# PetLaserBolt.net
KiCad netlist of a schematic drawn in Altium Designer
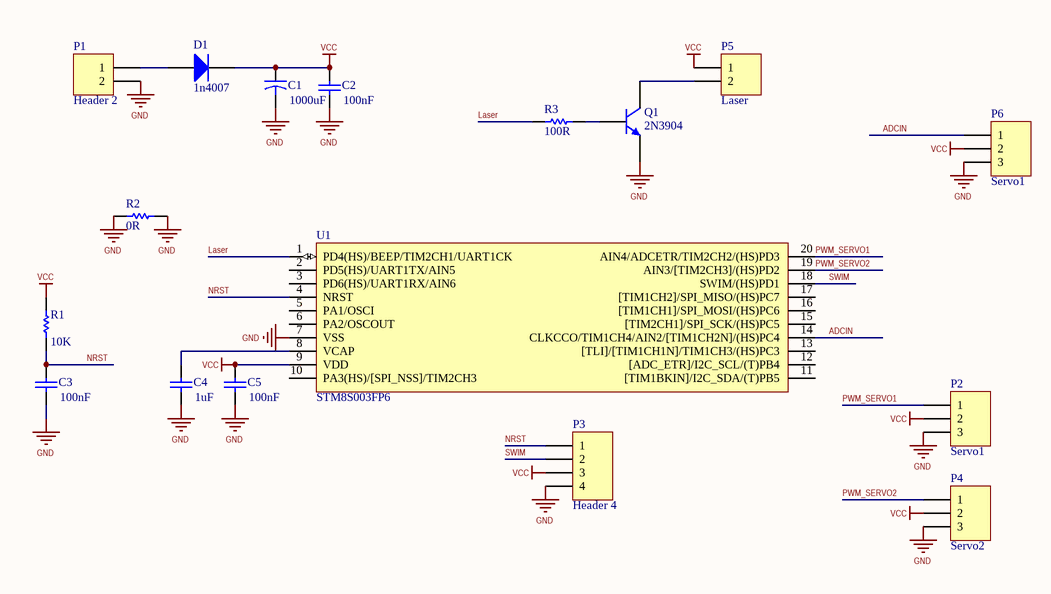
[diagram p0: PetLaserBolt.SchDoc]

(export (version "E")
  (design (tool "Eeschema 10.0.6"))
  (components
    (comp (ref "C1")
      (value "1000uF")
      (footprint "Cap electrolitic radial 10x16-5")
      (description "Capacitor")
      (fields (field (name "Comment") "Cap2") (field (name "PUBLISHER") "Altium Limited"))
      (libsource (lib "Miscellaneous Devices") (part "Cap2"))
    )
    (comp (ref "C2")
      (value "100nF")
      (footprint "CAP_MLCC_RAD_0.1")
      (description "Capacitor")
      (fields (field (name "Comment") "Cap") (field (name "PUBLISHER") "Altium Limited"))
      (libsource (lib "Miscellaneous Devices") (part "Cap"))
    )
    (comp (ref "C3")
      (value "100nF")
      (footprint "CAP_MLCC_RAD_0.1")
      (description "Capacitor")
      (fields (field (name "Comment") "Cap") (field (name "PUBLISHER") "Altium Limited"))
      (libsource (lib "Miscellaneous Devices") (part "Cap"))
    )
    (comp (ref "C4")
      (value "1uF")
      (footprint "CAP_MLCC_RAD_0.1")
      (description "Capacitor")
      (fields (field (name "Comment") "Cap") (field (name "PUBLISHER") "Altium Limited"))
      (libsource (lib "Miscellaneous Devices") (part "Cap"))
    )
    (comp (ref "C5")
      (value "100nF")
      (footprint "CAP_MLCC_RAD_0.1")
      (description "Capacitor")
      (fields (field (name "Comment") "Cap") (field (name "PUBLISHER") "Altium Limited"))
      (libsource (lib "Miscellaneous Devices") (part "Cap"))
    )
    (comp (ref "D1")
      (value "1n4007")
      (footprint "DO-204AL")
      (description "Default Diode")
      (fields (field (name "PUBLISHER") "Altium Limited"))
      (libsource (lib "Miscellaneous Devices") (part "Diode"))
    )
    (comp (ref "P1")
      (value "Header 2")
      (footprint "KF301 2PIN")
      (description "Header, 2-Pin")
      (fields (field (name "PUBLISHER") "Altium Limited"))
      (libsource (lib "Miscellaneous Connectors") (part "Header 2"))
    )
    (comp (ref "P2")
      (value "Servo1")
      (footprint "HDR_1x3")
      (description "Header, 3-Pin")
      (fields (field (name "PUBLISHER") "Altium Limited"))
      (libsource (lib "Miscellaneous Connectors") (part "Header 3"))
    )
    (comp (ref "P3")
      (value "Header 4")
      (footprint "HDR1X4")
      (description "Header, 4-Pin")
      (fields (field (name "PUBLISHER") "Altium Limited"))
      (libsource (lib "Miscellaneous Connectors") (part "Header 4"))
    )
    (comp (ref "P4")
      (value "Servo2")
      (footprint "HDR_1x3")
      (description "Header, 3-Pin")
      (fields (field (name "PUBLISHER") "Altium Limited"))
      (libsource (lib "Miscellaneous Connectors") (part "Header 3"))
    )
    (comp (ref "P5")
      (value "Laser")
      (footprint "KF301 2PIN")
      (description "Header, 2-Pin")
      (fields (field (name "PUBLISHER") "Altium Limited"))
      (libsource (lib "") (part "Header 2_1"))
    )
    (comp (ref "P6")
      (value "Servo1")
      (footprint "HDR_1x3")
      (description "Header, 3-Pin")
      (fields (field (name "PUBLISHER") "Altium Limited"))
      (libsource (lib "Miscellaneous Connectors") (part "Header 3"))
    )
    (comp (ref "Q1")
      (value "2N3904")
      (footprint "TO-92 STR")
      (description "NPN General Purpose Amplifier")
      (fields (field (name "PUBLISHER") "Altium Limited"))
      (libsource (lib "Miscellaneous Devices") (part "2N3904"))
    )
    (comp (ref "R1")
      (value "10K")
      (footprint "Axial 0_25 W, 0_4 IN LEAD PITCH")
      (description "Resistor")
      (fields (field (name "Comment") "Res1") (field (name "PUBLISHER") "Altium Limited"))
      (libsource (lib "Miscellaneous Devices") (part "Res1"))
    )
    (comp (ref "R2")
      (value "0R")
      (footprint "axial-0.3")
      (description "Resistor")
      (fields (field (name "Comment") "Res1") (field (name "PUBLISHER") "Altium Limited"))
      (libsource (lib "Miscellaneous Devices") (part "Res1"))
    )
    (comp (ref "R3")
      (value "100R")
      (footprint "Axial 0_25 W, 0_4 IN LEAD PITCH")
      (description "Resistor")
      (fields (field (name "Comment") "Res1") (field (name "PUBLISHER") "Altium Limited"))
      (libsource (lib "Miscellaneous Devices") (part "Res1"))
    )
    (comp (ref "U1")
      (value "STM8S003FP6")
      (footprint "TSSOP20")
      (description "8 bit microcontroller")
      (libsource (lib "Mofidi3D") (part "STM8S003F3Px"))
    )
  )
  (nets
    (net (code "1") (name "/ADCIN") (class "Default")
      (node (ref "P6") (pin "1") (pinfunction "1_1") (pintype "passive"))
      (node (ref "U1") (pin "14") (pinfunction "CLKCCO/TIM1CH4/AIN2/[TIM1CH2N]/(HS)PC4_14") (pintype "passive"))
    )
    (net (code "2") (name "/Laser") (class "Default")
      (node (ref "R3") (pin "2") (pinfunction "2_2") (pintype "passive"))
      (node (ref "U1") (pin "1") (pinfunction "PD4(HS)/BEEP/TIM2CH1/UART1CK_1") (pintype "bidirectional"))
    )
    (net (code "3") (name "/NRST") (class "Default")
      (node (ref "C3") (pin "2") (pinfunction "2_2") (pintype "passive"))
      (node (ref "P3") (pin "1") (pinfunction "1_1") (pintype "passive"))
      (node (ref "R1") (pin "1") (pinfunction "1_1") (pintype "passive"))
      (node (ref "U1") (pin "4") (pinfunction "NRST_4") (pintype "passive"))
    )
    (net (code "4") (name "/PWM_SERVO1") (class "Default")
      (node (ref "P2") (pin "1") (pinfunction "1_1") (pintype "passive"))
      (node (ref "U1") (pin "20") (pinfunction "AIN4/ADCETR/TIM2CH2/(HS)PD3_20") (pintype "passive"))
    )
    (net (code "5") (name "/PWM_SERVO2") (class "Default")
      (node (ref "P4") (pin "1") (pinfunction "1_1") (pintype "passive"))
      (node (ref "U1") (pin "19") (pinfunction "AIN3/[TIM2CH3]/(HS)PD2_19") (pintype "passive"))
    )
    (net (code "6") (name "/SWIM") (class "Default")
      (node (ref "P3") (pin "2") (pinfunction "2_2") (pintype "passive"))
      (node (ref "U1") (pin "18") (pinfunction "SWIM/(HS)PD1_18") (pintype "passive"))
    )
    (net (code "7") (name "GND") (class "Default")
      (node (ref "C1") (pin "2") (pinfunction "2_2") (pintype "passive"))
      (node (ref "C2") (pin "1") (pinfunction "1_1") (pintype "passive"))
      (node (ref "C3") (pin "1") (pinfunction "1_1") (pintype "passive"))
      (node (ref "C4") (pin "1") (pinfunction "1_1") (pintype "passive"))
      (node (ref "C5") (pin "1") (pinfunction "1_1") (pintype "passive"))
      (node (ref "P1") (pin "2") (pinfunction "2_2") (pintype "passive"))
      (node (ref "P2") (pin "3") (pinfunction "3_3") (pintype "passive"))
      (node (ref "P3") (pin "4") (pinfunction "4_4") (pintype "passive"))
      (node (ref "P4") (pin "3") (pinfunction "3_3") (pintype "passive"))
      (node (ref "P6") (pin "3") (pinfunction "3_3") (pintype "passive"))
      (node (ref "Q1") (pin "1") (pinfunction "E_1") (pintype "passive"))
      (node (ref "R2") (pin "1") (pinfunction "1_1") (pintype "passive"))
      (node (ref "R2") (pin "2") (pinfunction "2_2") (pintype "passive"))
      (node (ref "U1") (pin "7") (pinfunction "VSS_7") (pintype "passive"))
    )
    (net (code "8") (name "Net-(D1-A)") (class "Default")
      (node (ref "D1") (pin "1") (pinfunction "A_1") (pintype "passive"))
      (node (ref "P1") (pin "1") (pinfunction "1_1") (pintype "passive"))
    )
    (net (code "9") (name "Net-(Q1-B)") (class "Default")
      (node (ref "Q1") (pin "2") (pinfunction "B_2") (pintype "passive"))
      (node (ref "R3") (pin "1") (pinfunction "1_1") (pintype "passive"))
    )
    (net (code "10") (name "Net-(Q1-C)") (class "Default")
      (node (ref "P5") (pin "2") (pinfunction "2_2") (pintype "passive"))
      (node (ref "Q1") (pin "3") (pinfunction "C_3") (pintype "passive"))
    )
    (net (code "11") (name "Net-(U1-VCAP)") (class "Default")
      (node (ref "C4") (pin "2") (pinfunction "2_2") (pintype "passive"))
      (node (ref "U1") (pin "8") (pinfunction "VCAP_8") (pintype "passive"))
    )
    (net (code "12") (name "VCC") (class "Default")
      (node (ref "C1") (pin "1") (pinfunction "1_1") (pintype "passive"))
      (node (ref "C2") (pin "2") (pinfunction "2_2") (pintype "passive"))
      (node (ref "C5") (pin "2") (pinfunction "2_2") (pintype "passive"))
      (node (ref "D1") (pin "2") (pinfunction "K_2") (pintype "passive"))
      (node (ref "P2") (pin "2") (pinfunction "2_2") (pintype "passive"))
      (node (ref "P3") (pin "3") (pinfunction "3_3") (pintype "passive"))
      (node (ref "P4") (pin "2") (pinfunction "2_2") (pintype "passive"))
      (node (ref "P5") (pin "1") (pinfunction "1_1") (pintype "passive"))
      (node (ref "P6") (pin "2") (pinfunction "2_2") (pintype "passive"))
      (node (ref "R1") (pin "2") (pinfunction "2_2") (pintype "passive"))
      (node (ref "U1") (pin "9") (pinfunction "VDD_9") (pintype "passive"))
    )
    (net (code "13") (name "unconnected-(U1-PA1{slash}OSCI-Pad5)") (class "Default")
      (node (ref "U1") (pin "5") (pinfunction "PA1/OSCI_5") (pintype "passive"))
    )
    (net (code "14") (name "unconnected-(U1-PA2{slash}OSCOUT-Pad6)") (class "Default")
      (node (ref "U1") (pin "6") (pinfunction "PA2/OSCOUT_6") (pintype "passive"))
    )
    (net (code "15") (name "unconnected-(U1-PA3(HS){slash}[SPI_NSS]{slash}TIM2CH3-Pad10)") (class "Default")
      (node (ref "U1") (pin "10") (pinfunction "PA3(HS)/[SPI_NSS]/TIM2CH3_10") (pintype "passive"))
    )
    (net (code "16") (name "unconnected-(U1-PD5(HS){slash}UART1TX{slash}AIN5-Pad2)") (class "Default")
      (node (ref "U1") (pin "2") (pinfunction "PD5(HS)/UART1TX/AIN5_2") (pintype "passive"))
    )
    (net (code "17") (name "unconnected-(U1-PD6(HS){slash}UART1RX{slash}AIN6-Pad3)") (class "Default")
      (node (ref "U1") (pin "3") (pinfunction "PD6(HS)/UART1RX/AIN6_3") (pintype "passive"))
    )
    (net (code "18") (name "unconnected-(U1-[ADC_ETR]{slash}I2C_SCL{slash}(T)PB4-Pad12)") (class "Default")
      (node (ref "U1") (pin "12") (pinfunction "[ADC_ETR]/I2C_SCL/(T)PB4_12") (pintype "passive"))
    )
    (net (code "19") (name "unconnected-(U1-[TIM1BKIN]{slash}I2C_SDA{slash}(T)PB5-Pad11)") (class "Default")
      (node (ref "U1") (pin "11") (pinfunction "[TIM1BKIN]/I2C_SDA/(T)PB5_11") (pintype "passive"))
    )
    (net (code "20") (name "unconnected-(U1-[TIM1CH1]{slash}SPI_MOSI{slash}(HS)PC6-Pad16)") (class "Default")
      (node (ref "U1") (pin "16") (pinfunction "[TIM1CH1]/SPI_MOSI/(HS)PC6_16") (pintype "passive"))
    )
    (net (code "21") (name "unconnected-(U1-[TIM1CH2]{slash}SPI_MISO{slash}(HS)PC7-Pad17)") (class "Default")
      (node (ref "U1") (pin "17") (pinfunction "[TIM1CH2]/SPI_MISO/(HS)PC7_17") (pintype "passive"))
    )
    (net (code "22") (name "unconnected-(U1-[TIM2CH1]{slash}SPI_SCK{slash}(HS)PC5-Pad15)") (class "Default")
      (node (ref "U1") (pin "15") (pinfunction "[TIM2CH1]/SPI_SCK/(HS)PC5_15") (pintype "passive"))
    )
    (net (code "23") (name "unconnected-(U1-[TLI]{slash}[TIM1CH1N]{slash}TIM1CH3{slash}(HS)PC3-Pad13)") (class "Default")
      (node (ref "U1") (pin "13") (pinfunction "[TLI]/[TIM1CH1N]/TIM1CH3/(HS)PC3_13") (pintype "passive"))
    )
  )
)
